# PG8_ETHERNET.net
KiCad netlist of a schematic drawn in Altium Designer
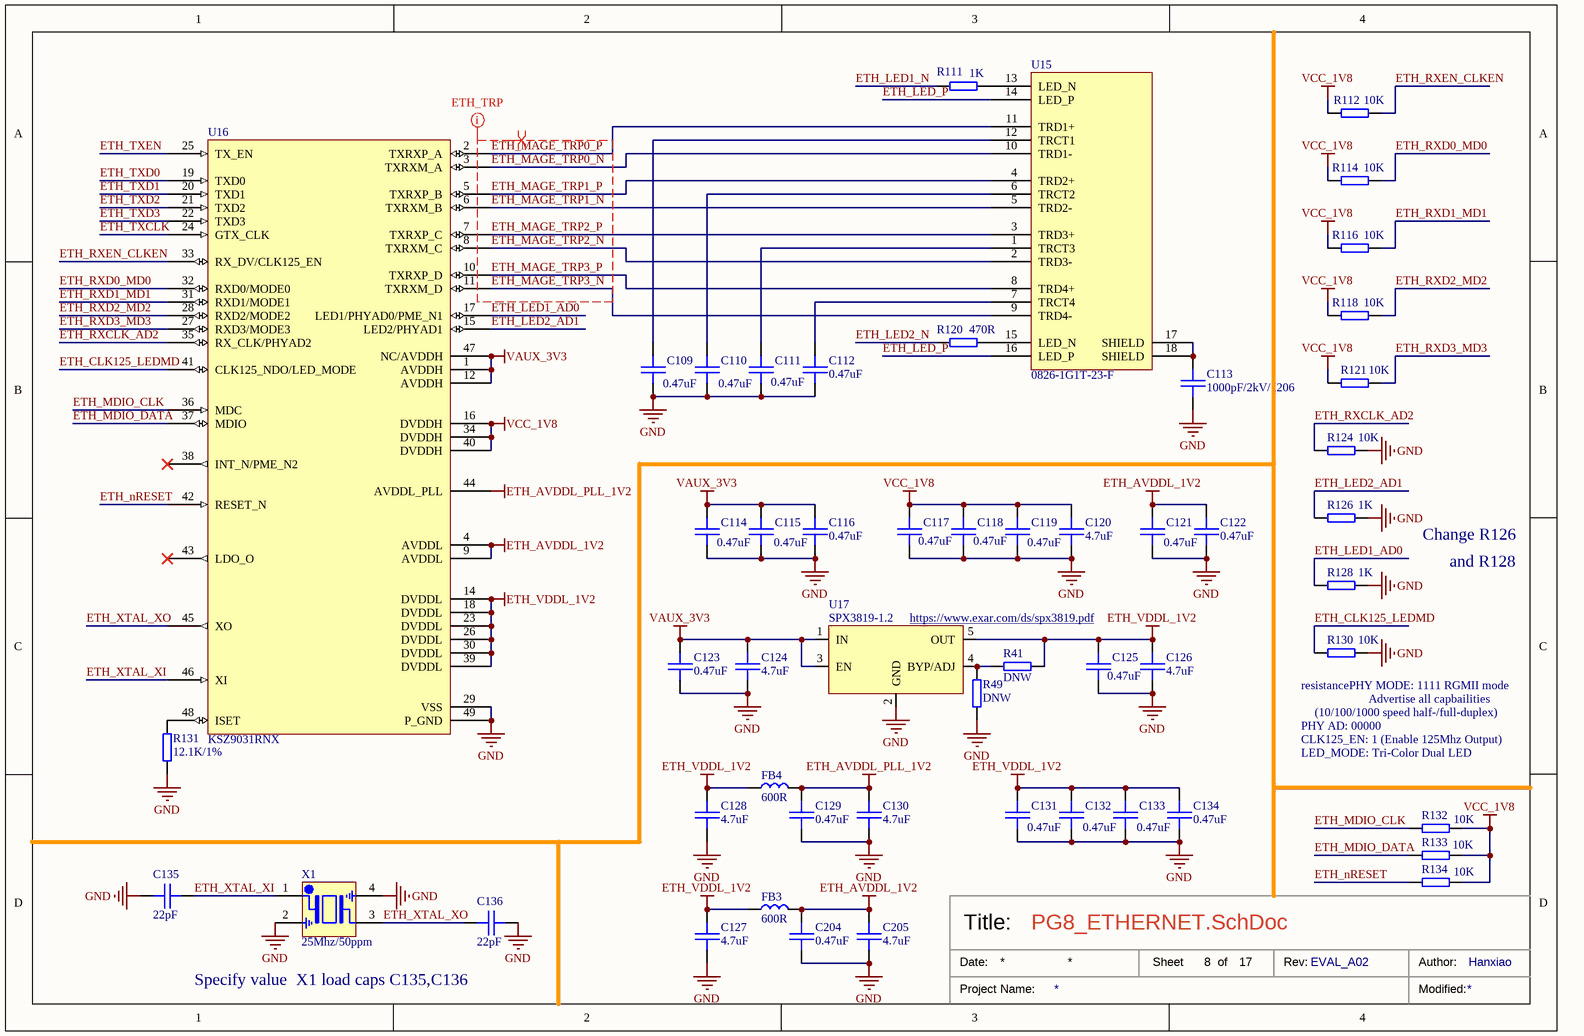
[diagram p0: PG8_ETHERNET.SchDoc]

(export (version "E")
  (design (tool "Eeschema 10.0.6"))
  (components
    (comp (ref "C109")
      (value "0.47uF")
      (footprint "SMT_C_0402")
      (description "Surface mount capacitor 0402")
      (libsource (lib "Vowstar_Basic_Device") (part "SMT_C_0402"))
    )
    (comp (ref "C110")
      (value "0.47uF")
      (footprint "SMT_C_0402")
      (description "Surface mount capacitor 0402")
      (libsource (lib "Vowstar_Basic_Device") (part "SMT_C_0402"))
    )
    (comp (ref "C111")
      (value "0.47uF")
      (footprint "SMT_C_0402")
      (description "Surface mount capacitor 0402")
      (libsource (lib "Vowstar_Basic_Device") (part "SMT_C_0402"))
    )
    (comp (ref "C112")
      (value "0.47uF")
      (footprint "SMT_C_0402")
      (description "Surface mount capacitor 0402")
      (libsource (lib "Vowstar_Basic_Device") (part "SMT_C_0402"))
    )
    (comp (ref "C113")
      (value "1000pF/2kV/1206")
      (footprint "CAPC3212X14N")
      (description "Surface mount capacitor 1206")
      (libsource (lib "Vowstar_Basic_Device") (part "SMT_C_0805"))
    )
    (comp (ref "C114")
      (value "0.47uF")
      (footprint "SMT_C_0402")
      (description "Surface mount capacitor 0402")
      (libsource (lib "Vowstar_Basic_Device") (part "SMT_C_0402"))
    )
    (comp (ref "C115")
      (value "0.47uF")
      (footprint "SMT_C_0402")
      (description "Surface mount capacitor 0402")
      (libsource (lib "Vowstar_Basic_Device") (part "SMT_C_0402"))
    )
    (comp (ref "C116")
      (value "0.47uF")
      (footprint "SMT_C_0402")
      (description "Surface mount capacitor 0402")
      (libsource (lib "Vowstar_Basic_Device") (part "SMT_C_0402"))
    )
    (comp (ref "C117")
      (value "0.47uF")
      (footprint "SMT_C_0402")
      (description "Surface mount capacitor 0402")
      (libsource (lib "Vowstar_Basic_Device") (part "SMT_C_0402"))
    )
    (comp (ref "C118")
      (value "0.47uF")
      (footprint "SMT_C_0402")
      (description "Surface mount capacitor 0402")
      (libsource (lib "Vowstar_Basic_Device") (part "SMT_C_0402"))
    )
    (comp (ref "C119")
      (value "0.47uF")
      (footprint "SMT_C_0402")
      (description "Surface mount capacitor 0402")
      (libsource (lib "Vowstar_Basic_Device") (part "SMT_C_0402"))
    )
    (comp (ref "C120")
      (value "4.7uF")
      (footprint "SMT_C_0402")
      (description "Surface mount capacitor 0402")
      (libsource (lib "Vowstar_Basic_Device") (part "SMT_C_0402"))
    )
    (comp (ref "C121")
      (value "0.47uF")
      (footprint "SMT_C_0402")
      (description "Surface mount capacitor 0402")
      (libsource (lib "Vowstar_Basic_Device") (part "SMT_C_0402"))
    )
    (comp (ref "C122")
      (value "0.47uF")
      (footprint "SMT_C_0402")
      (description "Surface mount capacitor 0402")
      (libsource (lib "Vowstar_Basic_Device") (part "SMT_C_0402"))
    )
    (comp (ref "C123")
      (value "0.47uF")
      (footprint "SMT_C_0402")
      (description "Surface mount capacitor 0402")
      (libsource (lib "Vowstar_Basic_Device") (part "SMT_C_0402"))
    )
    (comp (ref "C124")
      (value "4.7uF")
      (footprint "SMT_C_0402")
      (description "Surface mount capacitor 0402")
      (libsource (lib "Vowstar_Basic_Device") (part "SMT_C_0402"))
    )
    (comp (ref "C125")
      (value "0.47uF")
      (footprint "SMT_C_0402")
      (description "Surface mount capacitor 0402")
      (libsource (lib "Vowstar_Basic_Device") (part "SMT_C_0402"))
    )
    (comp (ref "C126")
      (value "4.7uF")
      (footprint "SMT_C_0402")
      (description "Surface mount capacitor 0402")
      (libsource (lib "Vowstar_Basic_Device") (part "SMT_C_0402"))
    )
    (comp (ref "C127")
      (value "4.7uF")
      (footprint "SMT_C_0402")
      (description "Surface mount capacitor 0402")
      (libsource (lib "Vowstar_Basic_Device") (part "SMT_C_0402"))
    )
    (comp (ref "C128")
      (value "4.7uF")
      (footprint "SMT_C_0402")
      (description "Surface mount capacitor 0402")
      (libsource (lib "Vowstar_Basic_Device") (part "SMT_C_0402"))
    )
    (comp (ref "C129")
      (value "0.47uF")
      (footprint "SMT_C_0402")
      (description "Surface mount capacitor 0402")
      (libsource (lib "Vowstar_Basic_Device") (part "SMT_C_0402"))
    )
    (comp (ref "C130")
      (value "4.7uF")
      (footprint "SMT_C_0402")
      (description "Surface mount capacitor 0402")
      (libsource (lib "Vowstar_Basic_Device") (part "SMT_C_0402"))
    )
    (comp (ref "C131")
      (value "0.47uF")
      (footprint "SMT_C_0402")
      (description "Surface mount capacitor 0402")
      (libsource (lib "Vowstar_Basic_Device") (part "SMT_C_0402"))
    )
    (comp (ref "C132")
      (value "0.47uF")
      (footprint "SMT_C_0402")
      (description "Surface mount capacitor 0402")
      (libsource (lib "Vowstar_Basic_Device") (part "SMT_C_0402"))
    )
    (comp (ref "C133")
      (value "0.47uF")
      (footprint "SMT_C_0402")
      (description "Surface mount capacitor 0402")
      (libsource (lib "Vowstar_Basic_Device") (part "SMT_C_0402"))
    )
    (comp (ref "C134")
      (value "0.47uF")
      (footprint "SMT_C_0402")
      (description "Surface mount capacitor 0402")
      (libsource (lib "Vowstar_Basic_Device") (part "SMT_C_0402"))
    )
    (comp (ref "C135")
      (value "22pF")
      (footprint "SMT_C_0402")
      (description "Surface mount capacitor 0402")
      (libsource (lib "Vowstar_Basic_Device") (part "SMT_C_0402"))
    )
    (comp (ref "C136")
      (value "22pF")
      (footprint "SMT_C_0402")
      (description "Surface mount capacitor 0402")
      (libsource (lib "Vowstar_Basic_Device") (part "SMT_C_0402"))
    )
    (comp (ref "C204")
      (value "0.47uF")
      (footprint "SMT_C_0402")
      (description "Surface mount capacitor 0402")
      (libsource (lib "Vowstar_Basic_Device") (part "SMT_C_0402"))
    )
    (comp (ref "C205")
      (value "4.7uF")
      (footprint "SMT_C_0402")
      (description "Surface mount capacitor 0402")
      (libsource (lib "Vowstar_Basic_Device") (part "SMT_C_0402"))
    )
    (comp (ref "FB3")
      (value "600R")
      (footprint "SMT_FB_0603")
      (description "Surface mount ferrite beads 0603")
      (libsource (lib "Vowstar_Basic_Device") (part "SMT_FB_0603"))
    )
    (comp (ref "FB4")
      (value "600R")
      (footprint "SMT_FB_0603")
      (description "Surface mount ferrite beads 0603")
      (libsource (lib "Vowstar_Basic_Device") (part "SMT_FB_0603"))
    )
    (comp (ref "R41")
      (value "DNW")
      (footprint "SMT_R_0402")
      (description "Surface mount resistor 0402")
      (libsource (lib "Vowstar_Basic_Device") (part "SMT_R_0402"))
    )
    (comp (ref "R49")
      (value "DNW")
      (footprint "SMT_R_0402")
      (description "Surface mount resistor 0402")
      (libsource (lib "Vowstar_Basic_Device") (part "SMT_R_0402"))
    )
    (comp (ref "R111")
      (value "1K")
      (footprint "SMT_R_0402")
      (description "Surface mount resistor 0402")
      (libsource (lib "Vowstar_Basic_Device") (part "SMT_R_0402"))
    )
    (comp (ref "R112")
      (value "10K")
      (footprint "SMT_R_0402")
      (description "Surface mount resistor 0402")
      (libsource (lib "Vowstar_Basic_Device") (part "SMT_R_0402"))
    )
    (comp (ref "R114")
      (value "10K")
      (footprint "SMT_R_0402")
      (description "Surface mount resistor 0402")
      (libsource (lib "Vowstar_Basic_Device") (part "SMT_R_0402"))
    )
    (comp (ref "R116")
      (value "10K")
      (footprint "SMT_R_0402")
      (description "Surface mount resistor 0402")
      (libsource (lib "Vowstar_Basic_Device") (part "SMT_R_0402"))
    )
    (comp (ref "R118")
      (value "10K")
      (footprint "SMT_R_0402")
      (description "Surface mount resistor 0402")
      (libsource (lib "Vowstar_Basic_Device") (part "SMT_R_0402"))
    )
    (comp (ref "R120")
      (value "470R")
      (footprint "SMT_R_0402")
      (description "Surface mount resistor 0402")
      (libsource (lib "Vowstar_Basic_Device") (part "SMT_R_0402"))
    )
    (comp (ref "R121")
      (value "10K")
      (footprint "SMT_R_0402")
      (description "Surface mount resistor 0402")
      (libsource (lib "Vowstar_Basic_Device") (part "SMT_R_0402"))
    )
    (comp (ref "R124")
      (value "10K")
      (footprint "SMT_R_0402")
      (description "Surface mount resistor 0402")
      (libsource (lib "Vowstar_Basic_Device") (part "SMT_R_0402"))
    )
    (comp (ref "R126")
      (value "1K")
      (footprint "SMT_R_0402")
      (description "Surface mount resistor 0402")
      (libsource (lib "Vowstar_Basic_Device") (part "SMT_R_0402"))
    )
    (comp (ref "R128")
      (value "1K")
      (footprint "SMT_R_0402")
      (description "Surface mount resistor 0402")
      (libsource (lib "Vowstar_Basic_Device") (part "SMT_R_0402"))
    )
    (comp (ref "R130")
      (value "10K")
      (footprint "SMT_R_0402")
      (description "Surface mount resistor 0402")
      (libsource (lib "Vowstar_Basic_Device") (part "SMT_R_0402"))
    )
    (comp (ref "R131")
      (value "12.1K/1%")
      (footprint "SMT_R_0402")
      (description "Surface mount resistor 0402")
      (libsource (lib "Vowstar_Basic_Device") (part "SMT_R_0402"))
    )
    (comp (ref "R132")
      (value "10K")
      (footprint "SMT_R_0402")
      (description "Surface mount resistor 0402")
      (libsource (lib "Vowstar_Basic_Device") (part "SMT_R_0402"))
    )
    (comp (ref "R133")
      (value "10K")
      (footprint "SMT_R_0402")
      (description "Surface mount resistor 0402")
      (libsource (lib "Vowstar_Basic_Device") (part "SMT_R_0402"))
    )
    (comp (ref "R134")
      (value "10K")
      (footprint "SMT_R_0402")
      (description "Surface mount resistor 0402")
      (libsource (lib "Vowstar_Basic_Device") (part "SMT_R_0402"))
    )
    (comp (ref "U15")
      (value "0826-1G1T-23-F")
      (footprint "0826-1G1T-23-F")
      (libsource (lib "LavasnowControllerHardware_EVAL_SCHLib_verA00") (part "0826-1G1T-23-F"))
    )
    (comp (ref "U16")
      (value "KSZ9031RNX")
      (footprint "QFN50P700X700X90_HS-49L")
      (description "Gigabit Ethernet Transceiver with RGMII\r\nSupport")
      (libsource (lib "LavasnowControllerHardware_EVAL_SCHLib_verA00") (part "KSZ9031RNX"))
    )
    (comp (ref "U17")
      (value "SPX3819-1.2")
      (footprint "SOT23-5")
      (description "500mA, Low-Noise LDO Voltage Regulator")
      (libsource (lib "Vowstar_IC_General") (part "SPX3819"))
    )
    (comp (ref "X1")
      (value "25Mhz/50ppm")
      (footprint "SMT_XTAL_3225")
      (description "Passive crystal")
      (libsource (lib "Vowstar_Basic_Device") (part "SMT_XTAL_PASSIVE"))
    )
  )
  (nets
    (net (code "1") (name "/ETH_CLK125_LEDMD") (class "Default")
      (node (ref "R130") (pin "1") (pinfunction "1_1") (pintype "passive"))
      (node (ref "U16") (pin "41") (pinfunction "CLK125_NDO/LED_MODE_41") (pintype "bidirectional"))
    )
    (net (code "2") (name "/ETH_LED1_AD0") (class "Default")
      (node (ref "R128") (pin "1") (pinfunction "1_1") (pintype "passive"))
      (node (ref "U16") (pin "17") (pinfunction "LED1/PHYAD0/PME_N1_17") (pintype "bidirectional"))
    )
    (net (code "3") (name "/ETH_LED1_N") (class "Default")
      (node (ref "R111") (pin "2") (pinfunction "2_2") (pintype "passive"))
    )
    (net (code "4") (name "/ETH_LED2_AD1") (class "Default")
      (node (ref "R126") (pin "1") (pinfunction "1_1") (pintype "passive"))
      (node (ref "U16") (pin "15") (pinfunction "LED2/PHYAD1_15") (pintype "bidirectional"))
    )
    (net (code "5") (name "/ETH_LED2_N") (class "Default")
      (node (ref "R120") (pin "2") (pinfunction "2_2") (pintype "passive"))
    )
    (net (code "6") (name "/ETH_LED_P") (class "Default")
      (node (ref "U15") (pin "14") (pinfunction "LED_P_14") (pintype "passive"))
      (node (ref "U15") (pin "16") (pinfunction "LED_P_16") (pintype "passive"))
    )
    (net (code "7") (name "/ETH_MAGE_TRP0_N") (class "Default")
      (node (ref "U15") (pin "10") (pinfunction "TRD1-_10") (pintype "passive"))
      (node (ref "U16") (pin "3") (pinfunction "TXRXM_A_3") (pintype "bidirectional"))
    )
    (net (code "8") (name "/ETH_MAGE_TRP0_P") (class "Default")
      (node (ref "U15") (pin "11") (pinfunction "TRD1+_11") (pintype "passive"))
      (node (ref "U16") (pin "2") (pinfunction "TXRXP_A_2") (pintype "bidirectional"))
    )
    (net (code "9") (name "/ETH_MAGE_TRP1_N") (class "Default")
      (node (ref "U15") (pin "5") (pinfunction "TRD2-_5") (pintype "passive"))
      (node (ref "U16") (pin "6") (pinfunction "TXRXM_B_6") (pintype "bidirectional"))
    )
    (net (code "10") (name "/ETH_MAGE_TRP1_P") (class "Default")
      (node (ref "U15") (pin "4") (pinfunction "TRD2+_4") (pintype "passive"))
      (node (ref "U16") (pin "5") (pinfunction "TXRXP_B_5") (pintype "bidirectional"))
    )
    (net (code "11") (name "/ETH_MAGE_TRP2_N") (class "Default")
      (node (ref "U15") (pin "2") (pinfunction "TRD3-_2") (pintype "passive"))
      (node (ref "U16") (pin "8") (pinfunction "TXRXM_C_8") (pintype "bidirectional"))
    )
    (net (code "12") (name "/ETH_MAGE_TRP2_P") (class "Default")
      (node (ref "U15") (pin "3") (pinfunction "TRD3+_3") (pintype "passive"))
      (node (ref "U16") (pin "7") (pinfunction "TXRXP_C_7") (pintype "bidirectional"))
    )
    (net (code "13") (name "/ETH_MAGE_TRP3_N") (class "Default")
      (node (ref "U15") (pin "9") (pinfunction "TRD4-_9") (pintype "passive"))
      (node (ref "U16") (pin "11") (pinfunction "TXRXM_D_11") (pintype "bidirectional"))
    )
    (net (code "14") (name "/ETH_MAGE_TRP3_P") (class "Default")
      (node (ref "U15") (pin "8") (pinfunction "TRD4+_8") (pintype "passive"))
      (node (ref "U16") (pin "10") (pinfunction "TXRXP_D_10") (pintype "bidirectional"))
    )
    (net (code "15") (name "/ETH_MDIO_CLK") (class "Default")
      (node (ref "R132") (pin "1") (pinfunction "1_1") (pintype "passive"))
      (node (ref "U16") (pin "36") (pinfunction "MDC_36") (pintype "input"))
    )
    (net (code "16") (name "/ETH_MDIO_DATA") (class "Default")
      (node (ref "R133") (pin "1") (pinfunction "1_1") (pintype "passive"))
      (node (ref "U16") (pin "37") (pinfunction "MDIO_37") (pintype "bidirectional"))
    )
    (net (code "17") (name "/ETH_RXCLK_AD2") (class "Default")
      (node (ref "R124") (pin "1") (pinfunction "1_1") (pintype "passive"))
      (node (ref "U16") (pin "35") (pinfunction "RX_CLK/PHYAD2_35") (pintype "bidirectional"))
    )
    (net (code "18") (name "/ETH_RXD0_MD0") (class "Default")
      (node (ref "R114") (pin "2") (pinfunction "2_2") (pintype "passive"))
      (node (ref "U16") (pin "32") (pinfunction "RXD0/MODE0_32") (pintype "bidirectional"))
    )
    (net (code "19") (name "/ETH_RXD1_MD1") (class "Default")
      (node (ref "R116") (pin "2") (pinfunction "2_2") (pintype "passive"))
      (node (ref "U16") (pin "31") (pinfunction "RXD1/MODE1_31") (pintype "bidirectional"))
    )
    (net (code "20") (name "/ETH_RXD2_MD2") (class "Default")
      (node (ref "R118") (pin "2") (pinfunction "2_2") (pintype "passive"))
      (node (ref "U16") (pin "28") (pinfunction "RXD2/MODE2_28") (pintype "bidirectional"))
    )
    (net (code "21") (name "/ETH_RXD3_MD3") (class "Default")
      (node (ref "R121") (pin "2") (pinfunction "2_2") (pintype "passive"))
      (node (ref "U16") (pin "27") (pinfunction "RXD3/MODE3_27") (pintype "bidirectional"))
    )
    (net (code "22") (name "/ETH_RXEN_CLKEN") (class "Default")
      (node (ref "R112") (pin "2") (pinfunction "2_2") (pintype "passive"))
      (node (ref "U16") (pin "33") (pinfunction "RX_DV/CLK125_EN_33") (pintype "bidirectional"))
    )
    (net (code "23") (name "/ETH_TXCLK") (class "Default")
      (node (ref "U16") (pin "24") (pinfunction "GTX_CLK_24") (pintype "input"))
    )
    (net (code "24") (name "/ETH_TXD0") (class "Default")
      (node (ref "U16") (pin "19") (pinfunction "TXD0_19") (pintype "input"))
    )
    (net (code "25") (name "/ETH_TXD1") (class "Default")
      (node (ref "U16") (pin "20") (pinfunction "TXD1_20") (pintype "input"))
    )
    (net (code "26") (name "/ETH_TXD2") (class "Default")
      (node (ref "U16") (pin "21") (pinfunction "TXD2_21") (pintype "input"))
    )
    (net (code "27") (name "/ETH_TXD3") (class "Default")
      (node (ref "U16") (pin "22") (pinfunction "TXD3_22") (pintype "input"))
    )
    (net (code "28") (name "/ETH_TXEN") (class "Default")
      (node (ref "U16") (pin "25") (pinfunction "TX_EN_25") (pintype "input"))
    )
    (net (code "29") (name "/ETH_XTAL_XI") (class "Default")
      (node (ref "C135") (pin "2") (pinfunction "2_2") (pintype "passive"))
      (node (ref "U16") (pin "46") (pinfunction "XI_46") (pintype "input"))
      (node (ref "X1") (pin "1") (pinfunction "IN/OUT_1") (pintype "passive"))
    )
    (net (code "30") (name "/ETH_XTAL_XO") (class "Default")
      (node (ref "C136") (pin "1") (pinfunction "1_1") (pintype "passive"))
      (node (ref "U16") (pin "45") (pinfunction "XO_45") (pintype "output"))
      (node (ref "X1") (pin "3") (pinfunction "IN/OUT_3") (pintype "passive"))
    )
    (net (code "31") (name "/ETH_nRESET") (class "Default")
      (node (ref "R134") (pin "1") (pinfunction "1_1") (pintype "passive"))
      (node (ref "U16") (pin "42") (pinfunction "RESET_N_42") (pintype "input"))
    )
    (net (code "32") (name "ETH_AVDDL_1V2") (class "Default")
      (node (ref "C121") (pin "1") (pinfunction "1_1") (pintype "passive"))
      (node (ref "C122") (pin "1") (pinfunction "1_1") (pintype "passive"))
      (node (ref "C204") (pin "1") (pinfunction "1_1") (pintype "passive"))
      (node (ref "C205") (pin "1") (pinfunction "1_1") (pintype "passive"))
      (node (ref "FB3") (pin "1") (pinfunction "1_1") (pintype "passive"))
      (node (ref "U16") (pin "4") (pinfunction "AVDDL_4") (pintype "power_in"))
      (node (ref "U16") (pin "9") (pinfunction "AVDDL_9") (pintype "power_in"))
    )
    (net (code "33") (name "ETH_AVDDL_PLL_1V2") (class "Default")
      (node (ref "C129") (pin "1") (pinfunction "1_1") (pintype "passive"))
      (node (ref "C130") (pin "1") (pinfunction "1_1") (pintype "passive"))
      (node (ref "FB4") (pin "1") (pinfunction "1_1") (pintype "passive"))
      (node (ref "U16") (pin "44") (pinfunction "AVDDL_PLL_44") (pintype "power_in"))
    )
    (net (code "34") (name "ETH_VDDL_1V2") (class "Default")
      (node (ref "C125") (pin "1") (pinfunction "1_1") (pintype "passive"))
      (node (ref "C126") (pin "1") (pinfunction "1_1") (pintype "passive"))
      (node (ref "C127") (pin "1") (pinfunction "1_1") (pintype "passive"))
      (node (ref "C128") (pin "1") (pinfunction "1_1") (pintype "passive"))
      (node (ref "C131") (pin "1") (pinfunction "1_1") (pintype "passive"))
      (node (ref "C132") (pin "1") (pinfunction "1_1") (pintype "passive"))
      (node (ref "C133") (pin "1") (pinfunction "1_1") (pintype "passive"))
      (node (ref "C134") (pin "1") (pinfunction "1_1") (pintype "passive"))
      (node (ref "FB3") (pin "2") (pinfunction "2_2") (pintype "passive"))
      (node (ref "FB4") (pin "2") (pinfunction "2_2") (pintype "passive"))
      (node (ref "R41") (pin "2") (pinfunction "2_2") (pintype "passive"))
      (node (ref "U16") (pin "14") (pinfunction "DVDDL_14") (pintype "power_in"))
      (node (ref "U16") (pin "18") (pinfunction "DVDDL_18") (pintype "power_in"))
      (node (ref "U16") (pin "23") (pinfunction "DVDDL_23") (pintype "power_in"))
      (node (ref "U16") (pin "26") (pinfunction "DVDDL_26") (pintype "power_in"))
      (node (ref "U16") (pin "30") (pinfunction "DVDDL_30") (pintype "power_in"))
      (node (ref "U16") (pin "39") (pinfunction "DVDDL_39") (pintype "power_in"))
      (node (ref "U17") (pin "5") (pinfunction "OUT_5") (pintype "passive"))
    )
    (net (code "35") (name "GND") (class "Default")
      (node (ref "C109") (pin "2") (pinfunction "2_2") (pintype "passive"))
      (node (ref "C110") (pin "2") (pinfunction "2_2") (pintype "passive"))
      (node (ref "C111") (pin "2") (pinfunction "2_2") (pintype "passive"))
      (node (ref "C112") (pin "2") (pinfunction "2_2") (pintype "passive"))
      (node (ref "C113") (pin "2") (pinfunction "2_2") (pintype "passive"))
      (node (ref "C114") (pin "2") (pinfunction "2_2") (pintype "passive"))
      (node (ref "C115") (pin "2") (pinfunction "2_2") (pintype "passive"))
      (node (ref "C116") (pin "2") (pinfunction "2_2") (pintype "passive"))
      (node (ref "C117") (pin "2") (pinfunction "2_2") (pintype "passive"))
      (node (ref "C118") (pin "2") (pinfunction "2_2") (pintype "passive"))
      (node (ref "C119") (pin "2") (pinfunction "2_2") (pintype "passive"))
      (node (ref "C120") (pin "2") (pinfunction "2_2") (pintype "passive"))
      (node (ref "C121") (pin "2") (pinfunction "2_2") (pintype "passive"))
      (node (ref "C122") (pin "2") (pinfunction "2_2") (pintype "passive"))
      (node (ref "C123") (pin "2") (pinfunction "2_2") (pintype "passive"))
      (node (ref "C124") (pin "2") (pinfunction "2_2") (pintype "passive"))
      (node (ref "C125") (pin "2") (pinfunction "2_2") (pintype "passive"))
      (node (ref "C126") (pin "2") (pinfunction "2_2") (pintype "passive"))
      (node (ref "C127") (pin "2") (pinfunction "2_2") (pintype "passive"))
      (node (ref "C128") (pin "2") (pinfunction "2_2") (pintype "passive"))
      (node (ref "C129") (pin "2") (pinfunction "2_2") (pintype "passive"))
      (node (ref "C130") (pin "2") (pinfunction "2_2") (pintype "passive"))
      (node (ref "C131") (pin "2") (pinfunction "2_2") (pintype "passive"))
      (node (ref "C132") (pin "2") (pinfunction "2_2") (pintype "passive"))
      (node (ref "C133") (pin "2") (pinfunction "2_2") (pintype "passive"))
      (node (ref "C134") (pin "2") (pinfunction "2_2") (pintype "passive"))
      (node (ref "C135") (pin "1") (pinfunction "1_1") (pintype "passive"))
      (node (ref "C136") (pin "2") (pinfunction "2_2") (pintype "passive"))
      (node (ref "C204") (pin "2") (pinfunction "2_2") (pintype "passive"))
      (node (ref "C205") (pin "2") (pinfunction "2_2") (pintype "passive"))
      (node (ref "R124") (pin "2") (pinfunction "2_2") (pintype "passive"))
      (node (ref "R126") (pin "2") (pinfunction "2_2") (pintype "passive"))
      (node (ref "R128") (pin "2") (pinfunction "2_2") (pintype "passive"))
      (node (ref "R130") (pin "2") (pinfunction "2_2") (pintype "passive"))
      (node (ref "R131") (pin "2") (pinfunction "2_2") (pintype "passive"))
      (node (ref "R49") (pin "2") (pinfunction "2_2") (pintype "passive"))
      (node (ref "U16") (pin "29") (pinfunction "VSS_29") (pintype "power_in"))
      (node (ref "U16") (pin "49") (pinfunction "P_GND_49") (pintype "power_in"))
      (node (ref "U17") (pin "2") (pinfunction "GND_2") (pintype "passive"))
      (node (ref "X1") (pin "2") (pinfunction "GND_2") (pintype "passive"))
      (node (ref "X1") (pin "4") (pinfunction "GND_4") (pintype "passive"))
    )
    (net (code "36") (name "Net-(C113-Pad1)") (class "Default")
      (node (ref "C113") (pin "1") (pinfunction "1_1") (pintype "passive"))
      (node (ref "U15") (pin "17") (pinfunction "SHIELD_17") (pintype "passive"))
      (node (ref "U15") (pin "18") (pinfunction "SHIELD_18") (pintype "passive"))
    )
    (net (code "37") (name "Net-(R111-Pad1)") (class "Default")
      (node (ref "R111") (pin "1") (pinfunction "1_1") (pintype "passive"))
      (node (ref "U15") (pin "13") (pinfunction "LED_N_13") (pintype "passive"))
    )
    (net (code "38") (name "Net-(R120-Pad1)") (class "Default")
      (node (ref "R120") (pin "1") (pinfunction "1_1") (pintype "passive"))
      (node (ref "U15") (pin "15") (pinfunction "LED_N_15") (pintype "passive"))
    )
    (net (code "39") (name "Net-(U15-TRCT1)") (class "Default")
      (node (ref "C109") (pin "1") (pinfunction "1_1") (pintype "passive"))
      (node (ref "U15") (pin "12") (pinfunction "TRCT1_12") (pintype "passive"))
    )
    (net (code "40") (name "Net-(U15-TRCT2)") (class "Default")
      (node (ref "C110") (pin "1") (pinfunction "1_1") (pintype "passive"))
      (node (ref "U15") (pin "6") (pinfunction "TRCT2_6") (pintype "passive"))
    )
    (net (code "41") (name "Net-(U15-TRCT3)") (class "Default")
      (node (ref "C111") (pin "1") (pinfunction "1_1") (pintype "passive"))
      (node (ref "U15") (pin "1") (pinfunction "TRCT3_1") (pintype "passive"))
    )
    (net (code "42") (name "Net-(U15-TRCT4)") (class "Default")
      (node (ref "C112") (pin "1") (pinfunction "1_1") (pintype "passive"))
      (node (ref "U15") (pin "7") (pinfunction "TRCT4_7") (pintype "passive"))
    )
    (net (code "43") (name "Net-(U16-ISET)") (class "Default")
      (node (ref "R131") (pin "1") (pinfunction "1_1") (pintype "passive"))
      (node (ref "U16") (pin "48") (pinfunction "ISET_48") (pintype "bidirectional"))
    )
    (net (code "44") (name "Net-(U17-BYP{slash}ADJ)") (class "Default")
      (node (ref "R41") (pin "1") (pinfunction "1_1") (pintype "passive"))
      (node (ref "R49") (pin "1") (pinfunction "1_1") (pintype "passive"))
      (node (ref "U17") (pin "4") (pinfunction "BYP/ADJ_4") (pintype "passive"))
    )
    (net (code "45") (name "VAUX_3V3") (class "Default")
      (node (ref "C114") (pin "1") (pinfunction "1_1") (pintype "passive"))
      (node (ref "C115") (pin "1") (pinfunction "1_1") (pintype "passive"))
      (node (ref "C116") (pin "1") (pinfunction "1_1") (pintype "passive"))
      (node (ref "C123") (pin "1") (pinfunction "1_1") (pintype "passive"))
      (node (ref "C124") (pin "1") (pinfunction "1_1") (pintype "passive"))
      (node (ref "U16") (pin "1") (pinfunction "AVDDH_1") (pintype "power_in"))
      (node (ref "U16") (pin "12") (pinfunction "AVDDH_12") (pintype "power_in"))
      (node (ref "U16") (pin "47") (pinfunction "NC/AVDDH_47") (pintype "passive"))
      (node (ref "U17") (pin "1") (pinfunction "IN_1") (pintype "passive"))
      (node (ref "U17") (pin "3") (pinfunction "EN_3") (pintype "passive"))
    )
    (net (code "46") (name "VCC_1V8") (class "Default")
      (node (ref "C117") (pin "1") (pinfunction "1_1") (pintype "passive"))
      (node (ref "C118") (pin "1") (pinfunction "1_1") (pintype "passive"))
      (node (ref "C119") (pin "1") (pinfunction "1_1") (pintype "passive"))
      (node (ref "C120") (pin "1") (pinfunction "1_1") (pintype "passive"))
      (node (ref "R112") (pin "1") (pinfunction "1_1") (pintype "passive"))
      (node (ref "R114") (pin "1") (pinfunction "1_1") (pintype "passive"))
      (node (ref "R116") (pin "1") (pinfunction "1_1") (pintype "passive"))
      (node (ref "R118") (pin "1") (pinfunction "1_1") (pintype "passive"))
      (node (ref "R121") (pin "1") (pinfunction "1_1") (pintype "passive"))
      (node (ref "R132") (pin "2") (pinfunction "2_2") (pintype "passive"))
      (node (ref "R133") (pin "2") (pinfunction "2_2") (pintype "passive"))
      (node (ref "R134") (pin "2") (pinfunction "2_2") (pintype "passive"))
      (node (ref "U16") (pin "16") (pinfunction "DVDDH_16") (pintype "power_in"))
      (node (ref "U16") (pin "34") (pinfunction "DVDDH_34") (pintype "power_in"))
      (node (ref "U16") (pin "40") (pinfunction "DVDDH_40") (pintype "power_in"))
    )
    (net (code "47") (name "unconnected-(U16-INT_N{slash}PME_N2-Pad38)") (class "Default")
      (node (ref "U16") (pin "38") (pinfunction "INT_N/PME_N2_38") (pintype "output+no_connect"))
    )
    (net (code "48") (name "unconnected-(U16-LDO_O-Pad43)") (class "Default")
      (node (ref "U16") (pin "43") (pinfunction "LDO_O_43") (pintype "output+no_connect"))
    )
  )
)
